# leds.net
KiCad netlist of a schematic drawn in EAGLE
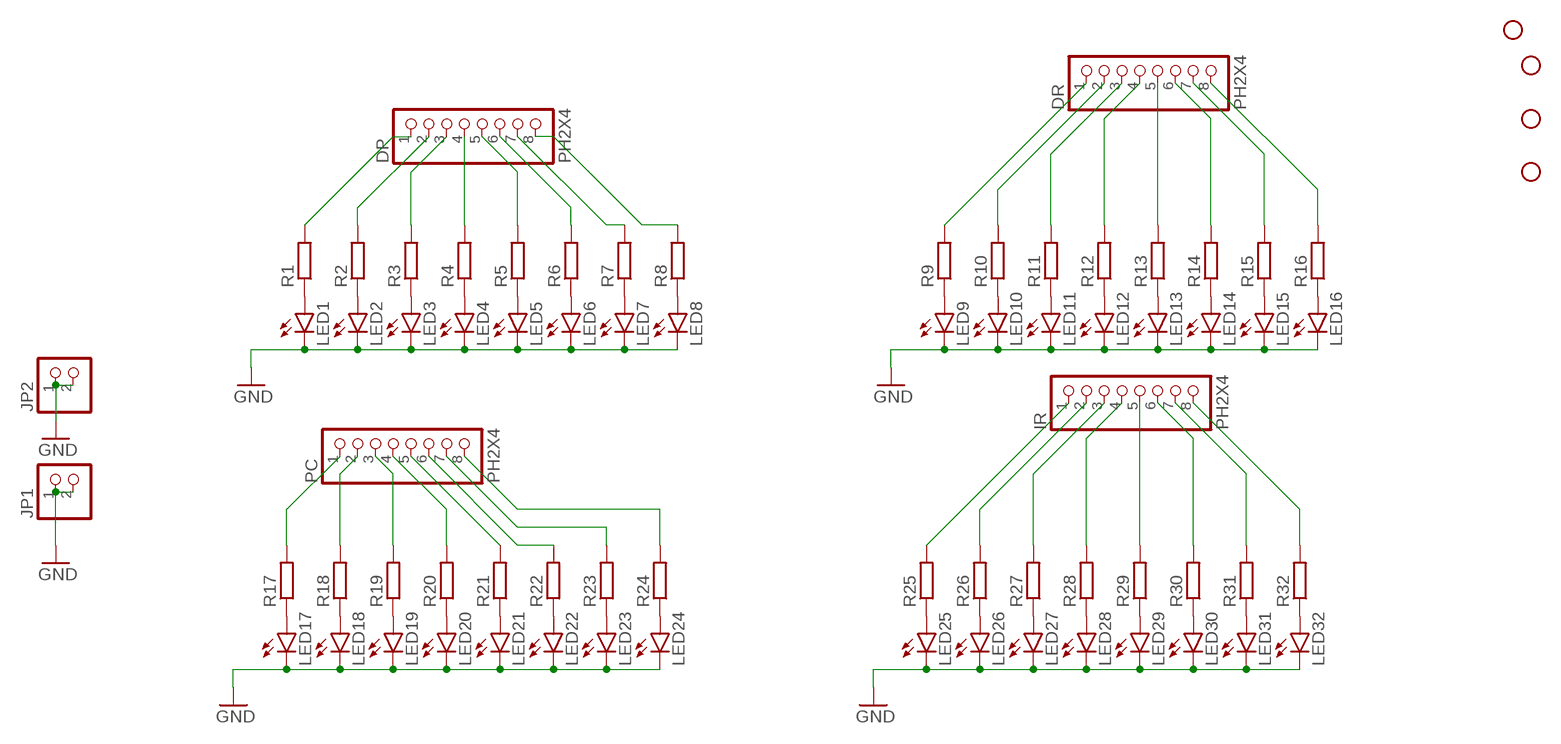
[diagram p0: schematic, sheet 1]

(export (version "E")
  (design (tool "Eeschema 10.0.6"))
  (components
    (comp (ref "DP")
      (value "PH2X4")
      (footprint "eagle-import:2X04")
      (libsource (lib "eagle-import") (part "PH2X4"))
    )
    (comp (ref "DR")
      (value "PH2X4")
      (footprint "eagle-import:2X04")
      (libsource (lib "eagle-import") (part "PH2X4"))
    )
    (comp (ref "H1")
      (value "STAND-OFF")
      (footprint "eagle-import:STAND-OFF")
      (libsource (lib "eagle-import") (part "STAND-OFF"))
    )
    (comp (ref "H2")
      (value "STAND-OFF")
      (footprint "eagle-import:STAND-OFF")
      (libsource (lib "eagle-import") (part "STAND-OFF"))
    )
    (comp (ref "H3")
      (value "STAND-OFF")
      (footprint "eagle-import:STAND-OFF")
      (libsource (lib "eagle-import") (part "STAND-OFF"))
    )
    (comp (ref "H4")
      (value "STAND-OFF")
      (footprint "eagle-import:STAND-OFF")
      (libsource (lib "eagle-import") (part "STAND-OFF"))
    )
    (comp (ref "IR")
      (value "PH2X4")
      (footprint "eagle-import:2X04")
      (libsource (lib "eagle-import") (part "PH2X4"))
    )
    (comp (ref "JP1")
      (value "PINHD-1X2")
      (footprint "eagle-import:1X02")
      (libsource (lib "eagle-import") (part "PINHD-1X2"))
    )
    (comp (ref "JP2")
      (value "PINHD-1X2")
      (footprint "eagle-import:1X02")
      (libsource (lib "eagle-import") (part "PINHD-1X2"))
    )
    (comp (ref "LED1")
      (value "LED5MM")
      (footprint "eagle-import:LED5MM")
      (libsource (lib "eagle-import") (part "LED5MM"))
    )
    (comp (ref "LED2")
      (value "LED5MM")
      (footprint "eagle-import:LED5MM")
      (libsource (lib "eagle-import") (part "LED5MM"))
    )
    (comp (ref "LED3")
      (value "LED5MM")
      (footprint "eagle-import:LED5MM")
      (libsource (lib "eagle-import") (part "LED5MM"))
    )
    (comp (ref "LED4")
      (value "LED5MM")
      (footprint "eagle-import:LED5MM")
      (libsource (lib "eagle-import") (part "LED5MM"))
    )
    (comp (ref "LED5")
      (value "LED5MM")
      (footprint "eagle-import:LED5MM")
      (libsource (lib "eagle-import") (part "LED5MM"))
    )
    (comp (ref "LED6")
      (value "LED5MM")
      (footprint "eagle-import:LED5MM")
      (libsource (lib "eagle-import") (part "LED5MM"))
    )
    (comp (ref "LED7")
      (value "LED5MM")
      (footprint "eagle-import:LED5MM")
      (libsource (lib "eagle-import") (part "LED5MM"))
    )
    (comp (ref "LED8")
      (value "LED5MM")
      (footprint "eagle-import:LED5MM")
      (libsource (lib "eagle-import") (part "LED5MM"))
    )
    (comp (ref "LED9")
      (value "LED5MM")
      (footprint "eagle-import:LED5MM")
      (libsource (lib "eagle-import") (part "LED5MM"))
    )
    (comp (ref "LED10")
      (value "LED5MM")
      (footprint "eagle-import:LED5MM")
      (libsource (lib "eagle-import") (part "LED5MM"))
    )
    (comp (ref "LED11")
      (value "LED5MM")
      (footprint "eagle-import:LED5MM")
      (libsource (lib "eagle-import") (part "LED5MM"))
    )
    (comp (ref "LED12")
      (value "LED5MM")
      (footprint "eagle-import:LED5MM")
      (libsource (lib "eagle-import") (part "LED5MM"))
    )
    (comp (ref "LED13")
      (value "LED5MM")
      (footprint "eagle-import:LED5MM")
      (libsource (lib "eagle-import") (part "LED5MM"))
    )
    (comp (ref "LED14")
      (value "LED5MM")
      (footprint "eagle-import:LED5MM")
      (libsource (lib "eagle-import") (part "LED5MM"))
    )
    (comp (ref "LED15")
      (value "LED5MM")
      (footprint "eagle-import:LED5MM")
      (libsource (lib "eagle-import") (part "LED5MM"))
    )
    (comp (ref "LED16")
      (value "LED5MM")
      (footprint "eagle-import:LED5MM")
      (libsource (lib "eagle-import") (part "LED5MM"))
    )
    (comp (ref "LED17")
      (value "LED5MM")
      (footprint "eagle-import:LED5MM")
      (libsource (lib "eagle-import") (part "LED5MM"))
    )
    (comp (ref "LED18")
      (value "LED5MM")
      (footprint "eagle-import:LED5MM")
      (libsource (lib "eagle-import") (part "LED5MM"))
    )
    (comp (ref "LED19")
      (value "LED5MM")
      (footprint "eagle-import:LED5MM")
      (libsource (lib "eagle-import") (part "LED5MM"))
    )
    (comp (ref "LED20")
      (value "LED5MM")
      (footprint "eagle-import:LED5MM")
      (libsource (lib "eagle-import") (part "LED5MM"))
    )
    (comp (ref "LED21")
      (value "LED5MM")
      (footprint "eagle-import:LED5MM")
      (libsource (lib "eagle-import") (part "LED5MM"))
    )
    (comp (ref "LED22")
      (value "LED5MM")
      (footprint "eagle-import:LED5MM")
      (libsource (lib "eagle-import") (part "LED5MM"))
    )
    (comp (ref "LED23")
      (value "LED5MM")
      (footprint "eagle-import:LED5MM")
      (libsource (lib "eagle-import") (part "LED5MM"))
    )
    (comp (ref "LED24")
      (value "LED5MM")
      (footprint "eagle-import:LED5MM")
      (libsource (lib "eagle-import") (part "LED5MM"))
    )
    (comp (ref "LED25")
      (value "LED5MM")
      (footprint "eagle-import:LED5MM")
      (libsource (lib "eagle-import") (part "LED5MM"))
    )
    (comp (ref "LED26")
      (value "LED5MM")
      (footprint "eagle-import:LED5MM")
      (libsource (lib "eagle-import") (part "LED5MM"))
    )
    (comp (ref "LED27")
      (value "LED5MM")
      (footprint "eagle-import:LED5MM")
      (libsource (lib "eagle-import") (part "LED5MM"))
    )
    (comp (ref "LED28")
      (value "LED5MM")
      (footprint "eagle-import:LED5MM")
      (libsource (lib "eagle-import") (part "LED5MM"))
    )
    (comp (ref "LED29")
      (value "LED5MM")
      (footprint "eagle-import:LED5MM")
      (libsource (lib "eagle-import") (part "LED5MM"))
    )
    (comp (ref "LED30")
      (value "LED5MM")
      (footprint "eagle-import:LED5MM")
      (libsource (lib "eagle-import") (part "LED5MM"))
    )
    (comp (ref "LED31")
      (value "LED5MM")
      (footprint "eagle-import:LED5MM")
      (libsource (lib "eagle-import") (part "LED5MM"))
    )
    (comp (ref "LED32")
      (value "LED5MM")
      (footprint "eagle-import:LED5MM")
      (libsource (lib "eagle-import") (part "LED5MM"))
    )
    (comp (ref "PC")
      (value "PH2X4")
      (footprint "eagle-import:2X04")
      (libsource (lib "eagle-import") (part "PH2X4"))
    )
    (comp (ref "R1")
      (value "R-EU_0204/5")
      (footprint "eagle-import:0204_5")
      (libsource (lib "eagle-import") (part "R-EU_0204/5"))
    )
    (comp (ref "R2")
      (value "R-EU_0204/5")
      (footprint "eagle-import:0204_5")
      (libsource (lib "eagle-import") (part "R-EU_0204/5"))
    )
    (comp (ref "R3")
      (value "R-EU_0204/5")
      (footprint "eagle-import:0204_5")
      (libsource (lib "eagle-import") (part "R-EU_0204/5"))
    )
    (comp (ref "R4")
      (value "R-EU_0204/5")
      (footprint "eagle-import:0204_5")
      (libsource (lib "eagle-import") (part "R-EU_0204/5"))
    )
    (comp (ref "R5")
      (value "R-EU_0204/5")
      (footprint "eagle-import:0204_5")
      (libsource (lib "eagle-import") (part "R-EU_0204/5"))
    )
    (comp (ref "R6")
      (value "R-EU_0204/5")
      (footprint "eagle-import:0204_5")
      (libsource (lib "eagle-import") (part "R-EU_0204/5"))
    )
    (comp (ref "R7")
      (value "R-EU_0204/5")
      (footprint "eagle-import:0204_5")
      (libsource (lib "eagle-import") (part "R-EU_0204/5"))
    )
    (comp (ref "R8")
      (value "R-EU_0204/5")
      (footprint "eagle-import:0204_5")
      (libsource (lib "eagle-import") (part "R-EU_0204/5"))
    )
    (comp (ref "R9")
      (value "R-EU_0204/5")
      (footprint "eagle-import:0204_5")
      (libsource (lib "eagle-import") (part "R-EU_0204/5"))
    )
    (comp (ref "R10")
      (value "R-EU_0204/5")
      (footprint "eagle-import:0204_5")
      (libsource (lib "eagle-import") (part "R-EU_0204/5"))
    )
    (comp (ref "R11")
      (value "R-EU_0204/5")
      (footprint "eagle-import:0204_5")
      (libsource (lib "eagle-import") (part "R-EU_0204/5"))
    )
    (comp (ref "R12")
      (value "R-EU_0204/5")
      (footprint "eagle-import:0204_5")
      (libsource (lib "eagle-import") (part "R-EU_0204/5"))
    )
    (comp (ref "R13")
      (value "R-EU_0204/5")
      (footprint "eagle-import:0204_5")
      (libsource (lib "eagle-import") (part "R-EU_0204/5"))
    )
    (comp (ref "R14")
      (value "R-EU_0204/5")
      (footprint "eagle-import:0204_5")
      (libsource (lib "eagle-import") (part "R-EU_0204/5"))
    )
    (comp (ref "R15")
      (value "R-EU_0204/5")
      (footprint "eagle-import:0204_5")
      (libsource (lib "eagle-import") (part "R-EU_0204/5"))
    )
    (comp (ref "R16")
      (value "R-EU_0204/5")
      (footprint "eagle-import:0204_5")
      (libsource (lib "eagle-import") (part "R-EU_0204/5"))
    )
    (comp (ref "R17")
      (value "R-EU_0204/5")
      (footprint "eagle-import:0204_5")
      (libsource (lib "eagle-import") (part "R-EU_0204/5"))
    )
    (comp (ref "R18")
      (value "R-EU_0204/5")
      (footprint "eagle-import:0204_5")
      (libsource (lib "eagle-import") (part "R-EU_0204/5"))
    )
    (comp (ref "R19")
      (value "R-EU_0204/5")
      (footprint "eagle-import:0204_5")
      (libsource (lib "eagle-import") (part "R-EU_0204/5"))
    )
    (comp (ref "R20")
      (value "R-EU_0204/5")
      (footprint "eagle-import:0204_5")
      (libsource (lib "eagle-import") (part "R-EU_0204/5"))
    )
    (comp (ref "R21")
      (value "R-EU_0204/5")
      (footprint "eagle-import:0204_5")
      (libsource (lib "eagle-import") (part "R-EU_0204/5"))
    )
    (comp (ref "R22")
      (value "R-EU_0204/5")
      (footprint "eagle-import:0204_5")
      (libsource (lib "eagle-import") (part "R-EU_0204/5"))
    )
    (comp (ref "R23")
      (value "R-EU_0204/5")
      (footprint "eagle-import:0204_5")
      (libsource (lib "eagle-import") (part "R-EU_0204/5"))
    )
    (comp (ref "R24")
      (value "R-EU_0204/5")
      (footprint "eagle-import:0204_5")
      (libsource (lib "eagle-import") (part "R-EU_0204/5"))
    )
    (comp (ref "R25")
      (value "R-EU_0204/5")
      (footprint "eagle-import:0204_5")
      (libsource (lib "eagle-import") (part "R-EU_0204/5"))
    )
    (comp (ref "R26")
      (value "R-EU_0204/5")
      (footprint "eagle-import:0204_5")
      (libsource (lib "eagle-import") (part "R-EU_0204/5"))
    )
    (comp (ref "R27")
      (value "R-EU_0204/5")
      (footprint "eagle-import:0204_5")
      (libsource (lib "eagle-import") (part "R-EU_0204/5"))
    )
    (comp (ref "R28")
      (value "R-EU_0204/5")
      (footprint "eagle-import:0204_5")
      (libsource (lib "eagle-import") (part "R-EU_0204/5"))
    )
    (comp (ref "R29")
      (value "R-EU_0204/5")
      (footprint "eagle-import:0204_5")
      (libsource (lib "eagle-import") (part "R-EU_0204/5"))
    )
    (comp (ref "R30")
      (value "R-EU_0204/5")
      (footprint "eagle-import:0204_5")
      (libsource (lib "eagle-import") (part "R-EU_0204/5"))
    )
    (comp (ref "R31")
      (value "R-EU_0204/5")
      (footprint "eagle-import:0204_5")
      (libsource (lib "eagle-import") (part "R-EU_0204/5"))
    )
    (comp (ref "R32")
      (value "R-EU_0204/5")
      (footprint "eagle-import:0204_5")
      (libsource (lib "eagle-import") (part "R-EU_0204/5"))
    )
  )
  (nets
    (net (code "1") (name "GND") (class "Default")
      (node (ref "JP1") (pin "1") (pinfunction "1_1") (pintype "passive"))
      (node (ref "JP1") (pin "2") (pinfunction "2_2") (pintype "passive"))
      (node (ref "JP2") (pin "1") (pinfunction "1_1") (pintype "passive"))
      (node (ref "JP2") (pin "2") (pinfunction "2_2") (pintype "passive"))
      (node (ref "LED1") (pin "K") (pinfunction "C_K") (pintype "passive"))
      (node (ref "LED10") (pin "K") (pinfunction "C_K") (pintype "passive"))
      (node (ref "LED11") (pin "K") (pinfunction "C_K") (pintype "passive"))
      (node (ref "LED12") (pin "K") (pinfunction "C_K") (pintype "passive"))
      (node (ref "LED13") (pin "K") (pinfunction "C_K") (pintype "passive"))
      (node (ref "LED14") (pin "K") (pinfunction "C_K") (pintype "passive"))
      (node (ref "LED15") (pin "K") (pinfunction "C_K") (pintype "passive"))
      (node (ref "LED16") (pin "K") (pinfunction "C_K") (pintype "passive"))
      (node (ref "LED17") (pin "K") (pinfunction "C_K") (pintype "passive"))
      (node (ref "LED18") (pin "K") (pinfunction "C_K") (pintype "passive"))
      (node (ref "LED19") (pin "K") (pinfunction "C_K") (pintype "passive"))
      (node (ref "LED2") (pin "K") (pinfunction "C_K") (pintype "passive"))
      (node (ref "LED20") (pin "K") (pinfunction "C_K") (pintype "passive"))
      (node (ref "LED21") (pin "K") (pinfunction "C_K") (pintype "passive"))
      (node (ref "LED22") (pin "K") (pinfunction "C_K") (pintype "passive"))
      (node (ref "LED23") (pin "K") (pinfunction "C_K") (pintype "passive"))
      (node (ref "LED24") (pin "K") (pinfunction "C_K") (pintype "passive"))
      (node (ref "LED25") (pin "K") (pinfunction "C_K") (pintype "passive"))
      (node (ref "LED26") (pin "K") (pinfunction "C_K") (pintype "passive"))
      (node (ref "LED27") (pin "K") (pinfunction "C_K") (pintype "passive"))
      (node (ref "LED28") (pin "K") (pinfunction "C_K") (pintype "passive"))
      (node (ref "LED29") (pin "K") (pinfunction "C_K") (pintype "passive"))
      (node (ref "LED3") (pin "K") (pinfunction "C_K") (pintype "passive"))
      (node (ref "LED30") (pin "K") (pinfunction "C_K") (pintype "passive"))
      (node (ref "LED31") (pin "K") (pinfunction "C_K") (pintype "passive"))
      (node (ref "LED32") (pin "K") (pinfunction "C_K") (pintype "passive"))
      (node (ref "LED4") (pin "K") (pinfunction "C_K") (pintype "passive"))
      (node (ref "LED5") (pin "K") (pinfunction "C_K") (pintype "passive"))
      (node (ref "LED6") (pin "K") (pinfunction "C_K") (pintype "passive"))
      (node (ref "LED7") (pin "K") (pinfunction "C_K") (pintype "passive"))
      (node (ref "LED8") (pin "K") (pinfunction "C_K") (pintype "passive"))
      (node (ref "LED9") (pin "K") (pinfunction "C_K") (pintype "passive"))
    )
    (net (code "2") (name "Net-(DP-Pad1)") (class "Default")
      (node (ref "DP") (pin "1") (pinfunction "1_1") (pintype "passive"))
      (node (ref "R1") (pin "2") (pinfunction "2_2") (pintype "passive"))
    )
    (net (code "3") (name "Net-(DP-Pad2)") (class "Default")
      (node (ref "DP") (pin "2") (pinfunction "2_2") (pintype "passive"))
      (node (ref "R2") (pin "2") (pinfunction "2_2") (pintype "passive"))
    )
    (net (code "4") (name "Net-(DP-Pad3)") (class "Default")
      (node (ref "DP") (pin "3") (pinfunction "3_3") (pintype "passive"))
      (node (ref "R3") (pin "2") (pinfunction "2_2") (pintype "passive"))
    )
    (net (code "5") (name "Net-(DP-Pad4)") (class "Default")
      (node (ref "DP") (pin "4") (pinfunction "4_4") (pintype "passive"))
      (node (ref "R4") (pin "2") (pinfunction "2_2") (pintype "passive"))
    )
    (net (code "6") (name "Net-(DP-Pad5)") (class "Default")
      (node (ref "DP") (pin "5") (pinfunction "5_5") (pintype "passive"))
      (node (ref "R5") (pin "2") (pinfunction "2_2") (pintype "passive"))
    )
    (net (code "7") (name "Net-(DP-Pad6)") (class "Default")
      (node (ref "DP") (pin "6") (pinfunction "6_6") (pintype "passive"))
      (node (ref "R6") (pin "2") (pinfunction "2_2") (pintype "passive"))
    )
    (net (code "8") (name "Net-(DP-Pad7)") (class "Default")
      (node (ref "DP") (pin "7") (pinfunction "7_7") (pintype "passive"))
      (node (ref "R7") (pin "2") (pinfunction "2_2") (pintype "passive"))
    )
    (net (code "9") (name "Net-(DP-Pad8)") (class "Default")
      (node (ref "DP") (pin "8") (pinfunction "8_8") (pintype "passive"))
      (node (ref "R8") (pin "2") (pinfunction "2_2") (pintype "passive"))
    )
    (net (code "10") (name "Net-(DR-Pad1)") (class "Default")
      (node (ref "DR") (pin "1") (pinfunction "1_1") (pintype "passive"))
      (node (ref "R9") (pin "2") (pinfunction "2_2") (pintype "passive"))
    )
    (net (code "11") (name "Net-(DR-Pad2)") (class "Default")
      (node (ref "DR") (pin "2") (pinfunction "2_2") (pintype "passive"))
      (node (ref "R10") (pin "2") (pinfunction "2_2") (pintype "passive"))
    )
    (net (code "12") (name "Net-(DR-Pad3)") (class "Default")
      (node (ref "DR") (pin "3") (pinfunction "3_3") (pintype "passive"))
      (node (ref "R11") (pin "2") (pinfunction "2_2") (pintype "passive"))
    )
    (net (code "13") (name "Net-(DR-Pad4)") (class "Default")
      (node (ref "DR") (pin "4") (pinfunction "4_4") (pintype "passive"))
      (node (ref "R12") (pin "2") (pinfunction "2_2") (pintype "passive"))
    )
    (net (code "14") (name "Net-(DR-Pad5)") (class "Default")
      (node (ref "DR") (pin "5") (pinfunction "5_5") (pintype "passive"))
      (node (ref "R13") (pin "2") (pinfunction "2_2") (pintype "passive"))
    )
    (net (code "15") (name "Net-(DR-Pad6)") (class "Default")
      (node (ref "DR") (pin "6") (pinfunction "6_6") (pintype "passive"))
      (node (ref "R14") (pin "2") (pinfunction "2_2") (pintype "passive"))
    )
    (net (code "16") (name "Net-(DR-Pad7)") (class "Default")
      (node (ref "DR") (pin "7") (pinfunction "7_7") (pintype "passive"))
      (node (ref "R15") (pin "2") (pinfunction "2_2") (pintype "passive"))
    )
    (net (code "17") (name "Net-(DR-Pad8)") (class "Default")
      (node (ref "DR") (pin "8") (pinfunction "8_8") (pintype "passive"))
      (node (ref "R16") (pin "2") (pinfunction "2_2") (pintype "passive"))
    )
    (net (code "18") (name "Net-(IR-Pad1)") (class "Default")
      (node (ref "IR") (pin "1") (pinfunction "1_1") (pintype "passive"))
      (node (ref "R25") (pin "2") (pinfunction "2_2") (pintype "passive"))
    )
    (net (code "19") (name "Net-(IR-Pad2)") (class "Default")
      (node (ref "IR") (pin "2") (pinfunction "2_2") (pintype "passive"))
      (node (ref "R26") (pin "2") (pinfunction "2_2") (pintype "passive"))
    )
    (net (code "20") (name "Net-(IR-Pad3)") (class "Default")
      (node (ref "IR") (pin "3") (pinfunction "3_3") (pintype "passive"))
      (node (ref "R27") (pin "2") (pinfunction "2_2") (pintype "passive"))
    )
    (net (code "21") (name "Net-(IR-Pad4)") (class "Default")
      (node (ref "IR") (pin "4") (pinfunction "4_4") (pintype "passive"))
      (node (ref "R28") (pin "2") (pinfunction "2_2") (pintype "passive"))
    )
    (net (code "22") (name "Net-(IR-Pad5)") (class "Default")
      (node (ref "IR") (pin "5") (pinfunction "5_5") (pintype "passive"))
      (node (ref "R29") (pin "2") (pinfunction "2_2") (pintype "passive"))
    )
    (net (code "23") (name "Net-(IR-Pad6)") (class "Default")
      (node (ref "IR") (pin "6") (pinfunction "6_6") (pintype "passive"))
      (node (ref "R30") (pin "2") (pinfunction "2_2") (pintype "passive"))
    )
    (net (code "24") (name "Net-(IR-Pad7)") (class "Default")
      (node (ref "IR") (pin "7") (pinfunction "7_7") (pintype "passive"))
      (node (ref "R31") (pin "2") (pinfunction "2_2") (pintype "passive"))
    )
    (net (code "25") (name "Net-(IR-Pad8)") (class "Default")
      (node (ref "IR") (pin "8") (pinfunction "8_8") (pintype "passive"))
      (node (ref "R32") (pin "2") (pinfunction "2_2") (pintype "passive"))
    )
    (net (code "26") (name "Net-(LED1-PadA)") (class "Default")
      (node (ref "LED1") (pin "A") (pinfunction "A_A") (pintype "passive"))
      (node (ref "R1") (pin "1") (pinfunction "1_1") (pintype "passive"))
    )
    (net (code "27") (name "Net-(LED2-PadA)") (class "Default")
      (node (ref "LED2") (pin "A") (pinfunction "A_A") (pintype "passive"))
      (node (ref "R2") (pin "1") (pinfunction "1_1") (pintype "passive"))
    )
    (net (code "28") (name "Net-(LED3-PadA)") (class "Default")
      (node (ref "LED3") (pin "A") (pinfunction "A_A") (pintype "passive"))
      (node (ref "R3") (pin "1") (pinfunction "1_1") (pintype "passive"))
    )
    (net (code "29") (name "Net-(LED4-PadA)") (class "Default")
      (node (ref "LED4") (pin "A") (pinfunction "A_A") (pintype "passive"))
      (node (ref "R4") (pin "1") (pinfunction "1_1") (pintype "passive"))
    )
    (net (code "30") (name "Net-(LED5-PadA)") (class "Default")
      (node (ref "LED5") (pin "A") (pinfunction "A_A") (pintype "passive"))
      (node (ref "R5") (pin "1") (pinfunction "1_1") (pintype "passive"))
    )
    (net (code "31") (name "Net-(LED6-PadA)") (class "Default")
      (node (ref "LED6") (pin "A") (pinfunction "A_A") (pintype "passive"))
      (node (ref "R6") (pin "1") (pinfunction "1_1") (pintype "passive"))
    )
    (net (code "32") (name "Net-(LED7-PadA)") (class "Default")
      (node (ref "LED7") (pin "A") (pinfunction "A_A") (pintype "passive"))
      (node (ref "R7") (pin "1") (pinfunction "1_1") (pintype "passive"))
    )
    (net (code "33") (name "Net-(LED8-PadA)") (class "Default")
      (node (ref "LED8") (pin "A") (pinfunction "A_A") (pintype "passive"))
      (node (ref "R8") (pin "1") (pinfunction "1_1") (pintype "passive"))
    )
    (net (code "34") (name "Net-(LED9-PadA)") (class "Default")
      (node (ref "LED9") (pin "A") (pinfunction "A_A") (pintype "passive"))
      (node (ref "R9") (pin "1") (pinfunction "1_1") (pintype "passive"))
    )
    (net (code "35") (name "Net-(LED10-PadA)") (class "Default")
      (node (ref "LED10") (pin "A") (pinfunction "A_A") (pintype "passive"))
      (node (ref "R10") (pin "1") (pinfunction "1_1") (pintype "passive"))
    )
    (net (code "36") (name "Net-(LED11-PadA)") (class "Default")
      (node (ref "LED11") (pin "A") (pinfunction "A_A") (pintype "passive"))
      (node (ref "R11") (pin "1") (pinfunction "1_1") (pintype "passive"))
    )
    (net (code "37") (name "Net-(LED12-PadA)") (class "Default")
      (node (ref "LED12") (pin "A") (pinfunction "A_A") (pintype "passive"))
      (node (ref "R12") (pin "1") (pinfunction "1_1") (pintype "passive"))
    )
    (net (code "38") (name "Net-(LED13-PadA)") (class "Default")
      (node (ref "LED13") (pin "A") (pinfunction "A_A") (pintype "passive"))
      (node (ref "R13") (pin "1") (pinfunction "1_1") (pintype "passive"))
    )
    (net (code "39") (name "Net-(LED14-PadA)") (class "Default")
      (node (ref "LED14") (pin "A") (pinfunction "A_A") (pintype "passive"))
      (node (ref "R14") (pin "1") (pinfunction "1_1") (pintype "passive"))
    )
    (net (code "40") (name "Net-(LED15-PadA)") (class "Default")
      (node (ref "LED15") (pin "A") (pinfunction "A_A") (pintype "passive"))
      (node (ref "R15") (pin "1") (pinfunction "1_1") (pintype "passive"))
    )
    (net (code "41") (name "Net-(LED16-PadA)") (class "Default")
      (node (ref "LED16") (pin "A") (pinfunction "A_A") (pintype "passive"))
      (node (ref "R16") (pin "1") (pinfunction "1_1") (pintype "passive"))
    )
    (net (code "42") (name "Net-(LED17-PadA)") (class "Default")
      (node (ref "LED17") (pin "A") (pinfunction "A_A") (pintype "passive"))
      (node (ref "R17") (pin "1") (pinfunction "1_1") (pintype "passive"))
    )
    (net (code "43") (name "Net-(LED18-PadA)") (class "Default")
      (node (ref "LED18") (pin "A") (pinfunction "A_A") (pintype "passive"))
      (node (ref "R18") (pin "1") (pinfunction "1_1") (pintype "passive"))
    )
    (net (code "44") (name "Net-(LED19-PadA)") (class "Default")
      (node (ref "LED19") (pin "A") (pinfunction "A_A") (pintype "passive"))
      (node (ref "R19") (pin "1") (pinfunction "1_1") (pintype "passive"))
    )
    (net (code "45") (name "Net-(LED20-PadA)") (class "Default")
      (node (ref "LED20") (pin "A") (pinfunction "A_A") (pintype "passive"))
      (node (ref "R20") (pin "1") (pinfunction "1_1") (pintype "passive"))
    )
    (net (code "46") (name "Net-(LED21-PadA)") (class "Default")
      (node (ref "LED21") (pin "A") (pinfunction "A_A") (pintype "passive"))
      (node (ref "R21") (pin "1") (pinfunction "1_1") (pintype "passive"))
    )
    (net (code "47") (name "Net-(LED22-PadA)") (class "Default")
      (node (ref "LED22") (pin "A") (pinfunction "A_A") (pintype "passive"))
      (node (ref "R22") (pin "1") (pinfunction "1_1") (pintype "passive"))
    )
    (net (code "48") (name "Net-(LED23-PadA)") (class "Default")
      (node (ref "LED23") (pin "A") (pinfunction "A_A") (pintype "passive"))
      (node (ref "R23") (pin "1") (pinfunction "1_1") (pintype "passive"))
    )
    (net (code "49") (name "Net-(LED24-PadA)") (class "Default")
      (node (ref "LED24") (pin "A") (pinfunction "A_A") (pintype "passive"))
      (node (ref "R24") (pin "1") (pinfunction "1_1") (pintype "passive"))
    )
    (net (code "50") (name "Net-(LED25-PadA)") (class "Default")
      (node (ref "LED25") (pin "A") (pinfunction "A_A") (pintype "passive"))
      (node (ref "R25") (pin "1") (pinfunction "1_1") (pintype "passive"))
    )
    (net (code "51") (name "Net-(LED26-PadA)") (class "Default")
      (node (ref "LED26") (pin "A") (pinfunction "A_A") (pintype "passive"))
      (node (ref "R26") (pin "1") (pinfunction "1_1") (pintype "passive"))
    )
    (net (code "52") (name "Net-(LED27-PadA)") (class "Default")
      (node (ref "LED27") (pin "A") (pinfunction "A_A") (pintype "passive"))
      (node (ref "R27") (pin "1") (pinfunction "1_1") (pintype "passive"))
    )
    (net (code "53") (name "Net-(LED28-PadA)") (class "Default")
      (node (ref "LED28") (pin "A") (pinfunction "A_A") (pintype "passive"))
      (node (ref "R28") (pin "1") (pinfunction "1_1") (pintype "passive"))
    )
    (net (code "54") (name "Net-(LED29-PadA)") (class "Default")
      (node (ref "LED29") (pin "A") (pinfunction "A_A") (pintype "passive"))
      (node (ref "R29") (pin "1") (pinfunction "1_1") (pintype "passive"))
    )
    (net (code "55") (name "Net-(LED30-PadA)") (class "Default")
      (node (ref "LED30") (pin "A") (pinfunction "A_A") (pintype "passive"))
      (node (ref "R30") (pin "1") (pinfunction "1_1") (pintype "passive"))
    )
    (net (code "56") (name "Net-(LED31-PadA)") (class "Default")
      (node (ref "LED31") (pin "A") (pinfunction "A_A") (pintype "passive"))
      (node (ref "R31") (pin "1") (pinfunction "1_1") (pintype "passive"))
    )
    (net (code "57") (name "Net-(LED32-PadA)") (class "Default")
      (node (ref "LED32") (pin "A") (pinfunction "A_A") (pintype "passive"))
      (node (ref "R32") (pin "1") (pinfunction "1_1") (pintype "passive"))
    )
    (net (code "58") (name "Net-(PC-Pad1)") (class "Default")
      (node (ref "PC") (pin "1") (pinfunction "1_1") (pintype "passive"))
      (node (ref "R17") (pin "2") (pinfunction "2_2") (pintype "passive"))
    )
    (net (code "59") (name "Net-(PC-Pad2)") (class "Default")
      (node (ref "PC") (pin "2") (pinfunction "2_2") (pintype "passive"))
      (node (ref "R18") (pin "2") (pinfunction "2_2") (pintype "passive"))
    )
    (net (code "60") (name "Net-(PC-Pad3)") (class "Default")
      (node (ref "PC") (pin "3") (pinfunction "3_3") (pintype "passive"))
      (node (ref "R19") (pin "2") (pinfunction "2_2") (pintype "passive"))
    )
    (net (code "61") (name "Net-(PC-Pad4)") (class "Default")
      (node (ref "PC") (pin "4") (pinfunction "4_4") (pintype "passive"))
      (node (ref "R20") (pin "2") (pinfunction "2_2") (pintype "passive"))
    )
    (net (code "62") (name "Net-(PC-Pad5)") (class "Default")
      (node (ref "PC") (pin "5") (pinfunction "5_5") (pintype "passive"))
      (node (ref "R21") (pin "2") (pinfunction "2_2") (pintype "passive"))
    )
    (net (code "63") (name "Net-(PC-Pad6)") (class "Default")
      (node (ref "PC") (pin "6") (pinfunction "6_6") (pintype "passive"))
      (node (ref "R22") (pin "2") (pinfunction "2_2") (pintype "passive"))
    )
    (net (code "64") (name "Net-(PC-Pad7)") (class "Default")
      (node (ref "PC") (pin "7") (pinfunction "7_7") (pintype "passive"))
      (node (ref "R23") (pin "2") (pinfunction "2_2") (pintype "passive"))
    )
    (net (code "65") (name "Net-(PC-Pad8)") (class "Default")
      (node (ref "PC") (pin "8") (pinfunction "8_8") (pintype "passive"))
      (node (ref "R24") (pin "2") (pinfunction "2_2") (pintype "passive"))
    )
  )
)
